# brick_i2c_compass_LSM303DLH.net
KiCad netlist of a schematic drawn in EAGLE
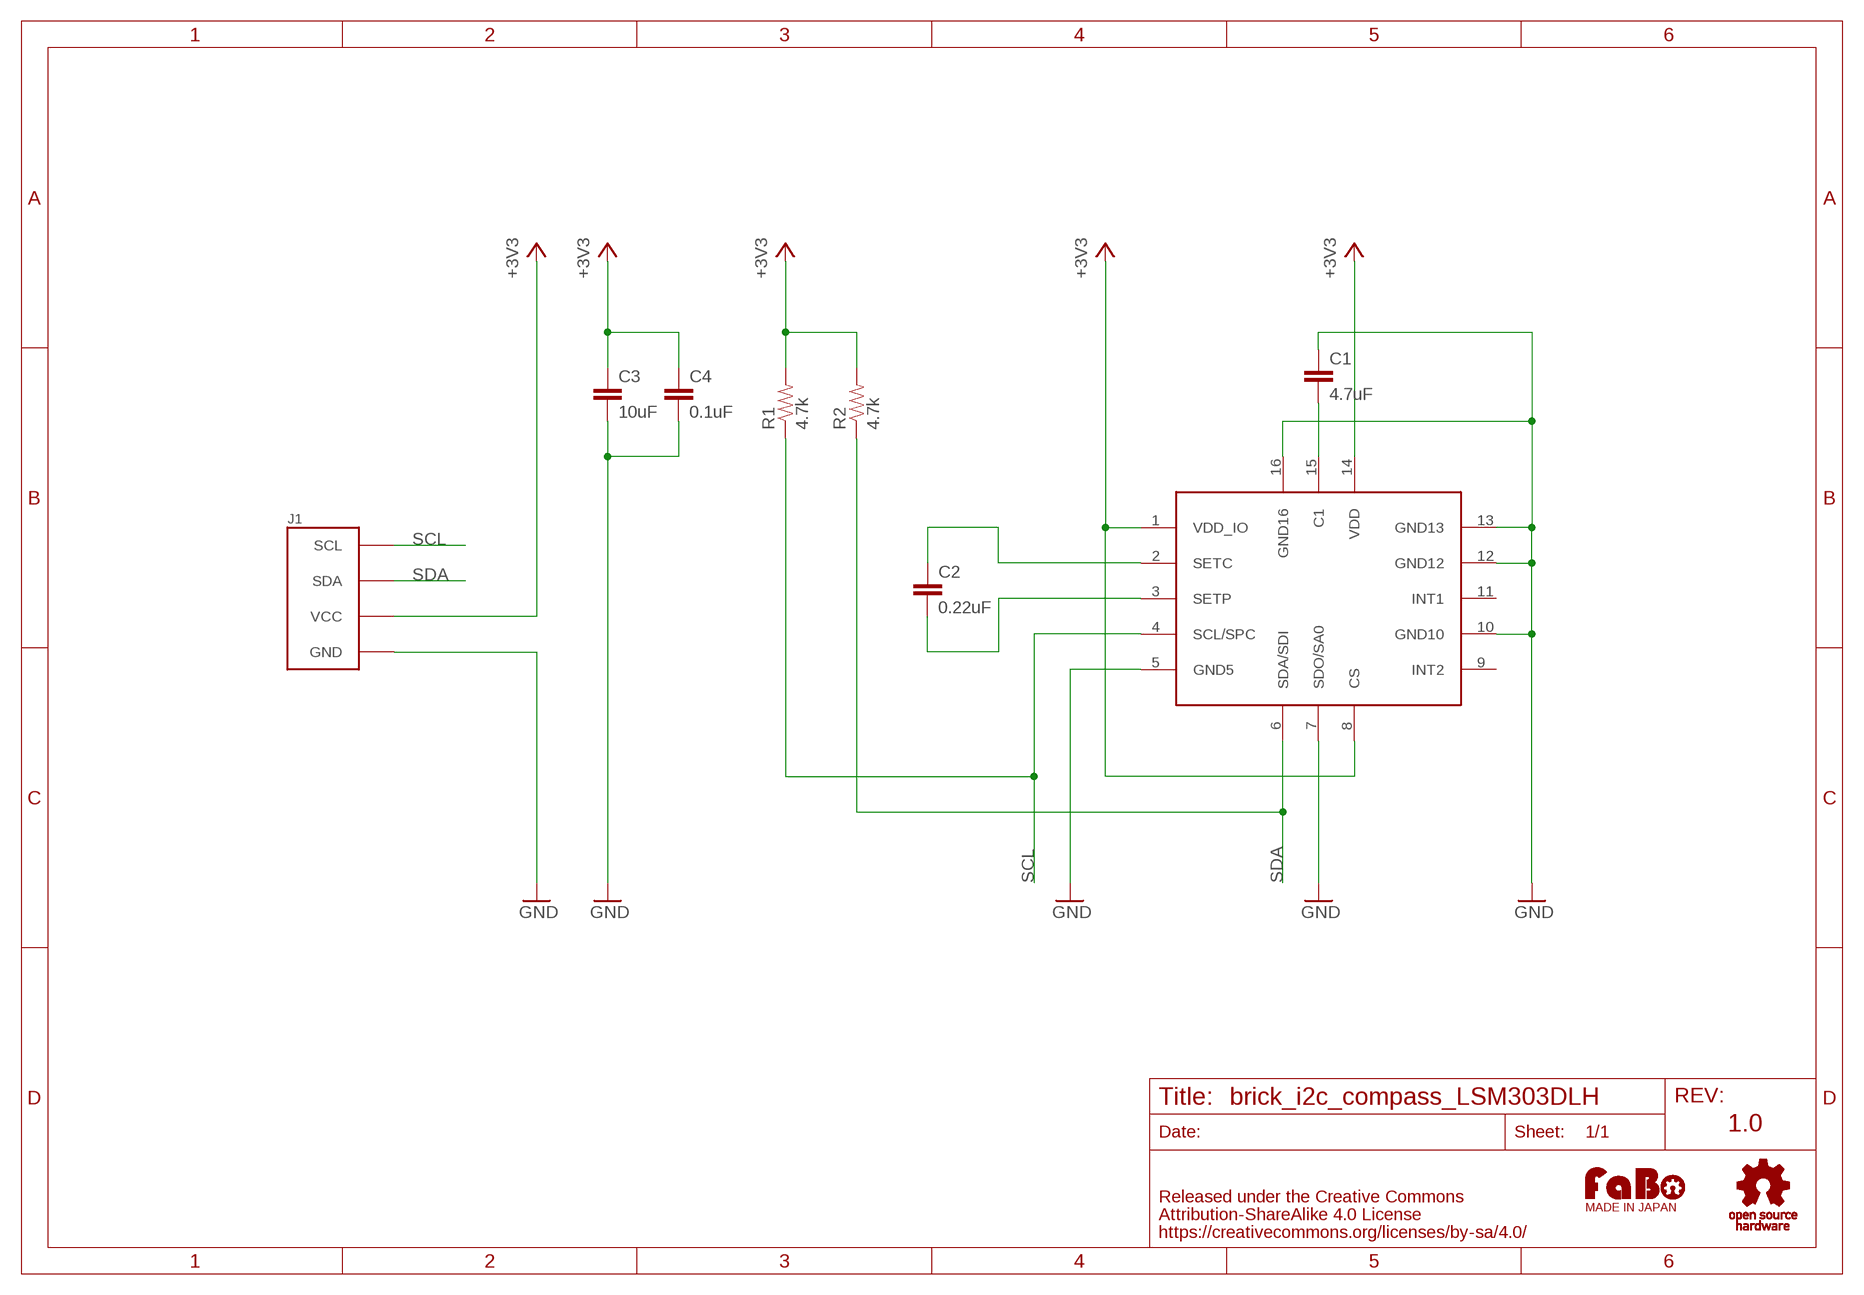
[diagram p0: schematic, sheet 1]

(export (version "E")
  (design (tool "Eeschema 10.0.6"))
  (components
    (comp (ref "C1")
      (value "4.7uF")
      (footprint "eagle-import:EIA0603")
      (libsource (lib "eagle-import") (part "CAP-EIA0603"))
    )
    (comp (ref "C2")
      (value "0.22uF")
      (footprint "eagle-import:EIA0603")
      (libsource (lib "eagle-import") (part "CAP-EIA0603"))
    )
    (comp (ref "C3")
      (value "10uF")
      (footprint "eagle-import:EIA0603")
      (libsource (lib "eagle-import") (part "CAP-EIA0603"))
    )
    (comp (ref "C4")
      (value "0.1uF")
      (footprint "eagle-import:EIA0603")
      (libsource (lib "eagle-import") (part "CAP-EIA0603"))
    )
    (comp (ref "J1")
      (value "BRICK_I2C")
      (footprint "eagle-import:BRICK_I2C")
      (libsource (lib "eagle-import") (part "BRICK_I2C"))
    )
    (comp (ref "R1")
      (value "4.7k")
      (footprint "eagle-import:EIA0603")
      (libsource (lib "eagle-import") (part "RES-EIA0603"))
    )
    (comp (ref "R2")
      (value "4.7k")
      (footprint "eagle-import:EIA0603")
      (libsource (lib "eagle-import") (part "RES-EIA0603"))
    )
    (comp (ref "U$2")
      (value "ST-LSM303DLH")
      (footprint "eagle-import:ST-LSM303DLH")
      (libsource (lib "eagle-import") (part "ST-LSM303DLH"))
    )
    (comp (ref "U$4")
      (value "LOGO_OSHW_T-M")
      (footprint "eagle-import:LOGO_OSHW_T_M")
      (libsource (lib "eagle-import") (part "LOGO_OSHW_T-M"))
    )
    (comp (ref "U$5")
      (value "LOGO_FABO-M")
      (footprint "eagle-import:LOGO_FABO_M")
      (libsource (lib "eagle-import") (part "LOGO_FABO-M"))
    )
  )
  (nets
    (net (code "1") (name "+3V3") (class "Default")
      (node (ref "C3") (pin "1") (pinfunction "1_1") (pintype "passive"))
      (node (ref "C4") (pin "1") (pinfunction "1_1") (pintype "passive"))
      (node (ref "J1") (pin "VCC") (pinfunction "VCC_VCC") (pintype "bidirectional"))
      (node (ref "R1") (pin "2") (pinfunction "2_2") (pintype "passive"))
      (node (ref "R2") (pin "2") (pinfunction "2_2") (pintype "passive"))
      (node (ref "U$2") (pin "1") (pinfunction "VDD_IO_1") (pintype "bidirectional"))
      (node (ref "U$2") (pin "14") (pinfunction "VDD_14") (pintype "bidirectional"))
      (node (ref "U$2") (pin "8") (pinfunction "CS_8") (pintype "bidirectional"))
    )
    (net (code "2") (name "/SCL") (class "Default")
      (node (ref "J1") (pin "SCL") (pinfunction "SCL_SCL") (pintype "bidirectional"))
      (node (ref "R1") (pin "1") (pinfunction "1_1") (pintype "passive"))
      (node (ref "U$2") (pin "4") (pinfunction "SCL/SPC_4") (pintype "bidirectional"))
    )
    (net (code "3") (name "/SDA") (class "Default")
      (node (ref "J1") (pin "SDA") (pinfunction "SDA_SDA") (pintype "bidirectional"))
      (node (ref "R2") (pin "1") (pinfunction "1_1") (pintype "passive"))
      (node (ref "U$2") (pin "6") (pinfunction "SDA/SDI_6") (pintype "bidirectional"))
    )
    (net (code "4") (name "GND") (class "Default")
      (node (ref "C1") (pin "1") (pinfunction "1_1") (pintype "passive"))
      (node (ref "C3") (pin "2") (pinfunction "2_2") (pintype "passive"))
      (node (ref "C4") (pin "2") (pinfunction "2_2") (pintype "passive"))
      (node (ref "J1") (pin "GND") (pinfunction "GND_GND") (pintype "bidirectional"))
      (node (ref "U$2") (pin "10") (pinfunction "GND10_10") (pintype "bidirectional"))
      (node (ref "U$2") (pin "12") (pinfunction "GND12_12") (pintype "bidirectional"))
      (node (ref "U$2") (pin "13") (pinfunction "GND13_13") (pintype "bidirectional"))
      (node (ref "U$2") (pin "16") (pinfunction "GND16_16") (pintype "bidirectional"))
      (node (ref "U$2") (pin "5") (pinfunction "GND5_5") (pintype "bidirectional"))
      (node (ref "U$2") (pin "7") (pinfunction "SDO/SA0_7") (pintype "bidirectional"))
    )
    (net (code "5") (name "Net-(U$2-C1)") (class "Default")
      (node (ref "C1") (pin "2") (pinfunction "2_2") (pintype "passive"))
      (node (ref "U$2") (pin "15") (pinfunction "C1_15") (pintype "bidirectional"))
    )
    (net (code "6") (name "Net-(U$2-SETC)") (class "Default")
      (node (ref "C2") (pin "1") (pinfunction "1_1") (pintype "passive"))
      (node (ref "U$2") (pin "2") (pinfunction "SETC_2") (pintype "bidirectional"))
    )
    (net (code "7") (name "Net-(U$2-SETP)") (class "Default")
      (node (ref "C2") (pin "2") (pinfunction "2_2") (pintype "passive"))
      (node (ref "U$2") (pin "3") (pinfunction "SETP_3") (pintype "bidirectional"))
    )
    (net (code "8") (name "unconnected-(U$2-INT1-Pad11)") (class "Default")
      (node (ref "U$2") (pin "11") (pinfunction "INT1_11") (pintype "bidirectional"))
    )
    (net (code "9") (name "unconnected-(U$2-INT2-Pad9)") (class "Default")
      (node (ref "U$2") (pin "9") (pinfunction "INT2_9") (pintype "bidirectional"))
    )
  )
)
